# Minimum_System_Destama_RN_21507334088.net
KiCad netlist of a schematic drawn in EAGLE
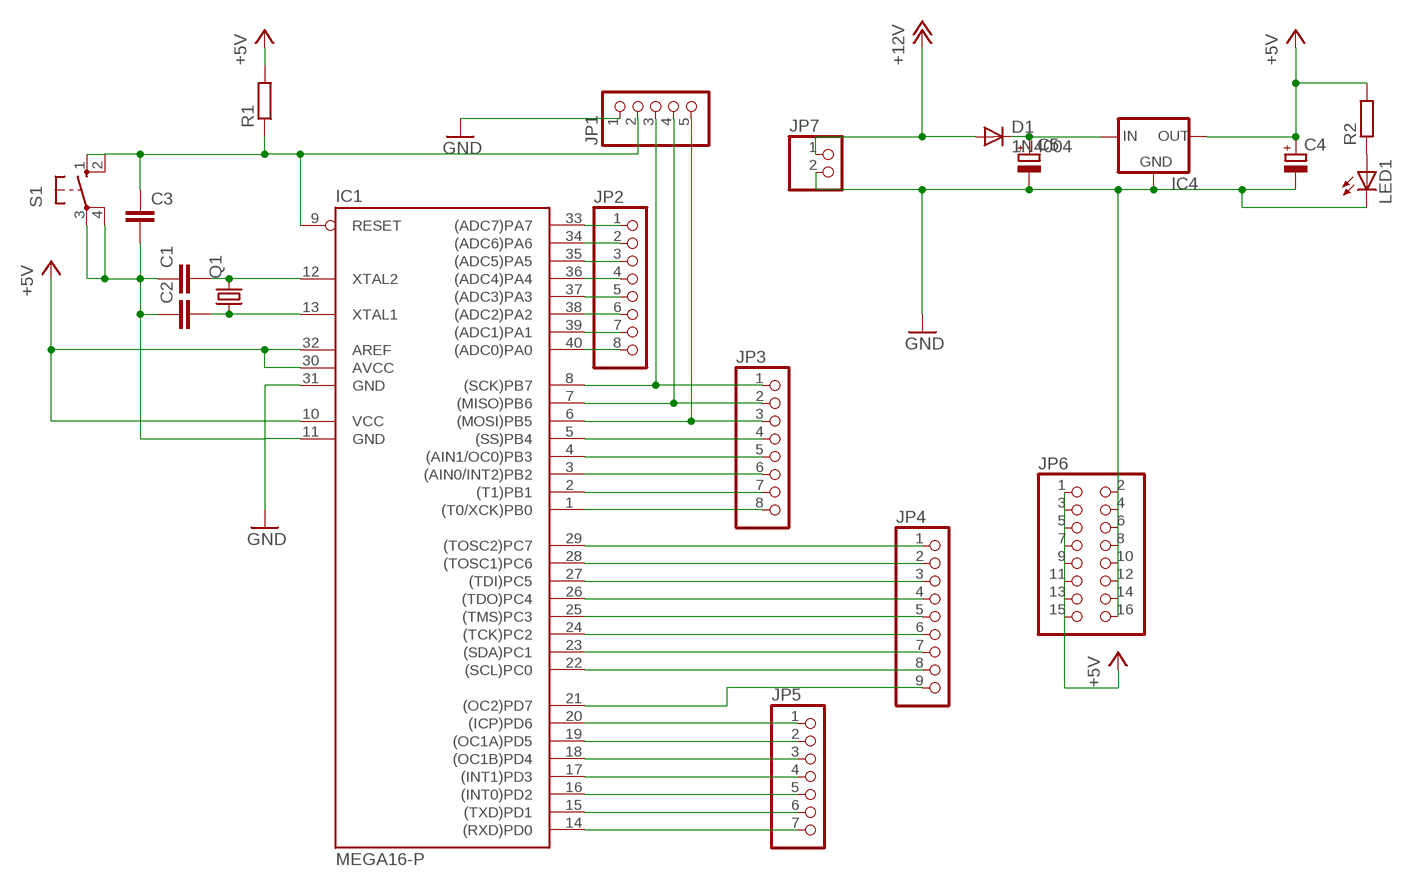
[diagram p0: schematic, sheet 1]

(export (version "E")
  (design (tool "Eeschema 10.0.6"))
  (components
    (comp (ref "C1")
      (value "C-EU025-024X044")
      (footprint "eagle-import:C025-024X044")
      (libsource (lib "eagle-import") (part "C-EU025-024X044"))
    )
    (comp (ref "C2")
      (value "C-EU025-024X044")
      (footprint "eagle-import:C025-024X044")
      (libsource (lib "eagle-import") (part "C-EU025-024X044"))
    )
    (comp (ref "C3")
      (value "C-EU050-025X075")
      (footprint "eagle-import:C050-025X075")
      (libsource (lib "eagle-import") (part "resistor_C-EU050-025X075"))
    )
    (comp (ref "C4")
      (value "CPOL-EUE2.5-5")
      (footprint "eagle-import:E2,5-5")
      (libsource (lib "eagle-import") (part "CPOL-EUE2.5-5"))
    )
    (comp (ref "C5")
      (value "CPOL-EUE2.5-5")
      (footprint "eagle-import:E2,5-5")
      (libsource (lib "eagle-import") (part "CPOL-EUE2.5-5"))
    )
    (comp (ref "D1")
      (value "1N4004")
      (footprint "eagle-import:DO41-10")
      (libsource (lib "eagle-import") (part "1N4004"))
    )
    (comp (ref "IC1")
      (value "MEGA16-P")
      (footprint "eagle-import:DIL40")
      (fields (field (name "MPN") "ATMEGA16-16PU"))
      (libsource (lib "eagle-import") (part "MEGA16-P"))
    )
    (comp (ref "IC4")
      (value "78XXS")
      (footprint "eagle-import:78XXS")
      (libsource (lib "eagle-import") (part "78XXS"))
    )
    (comp (ref "JP1")
      (value "PINHD-1X5")
      (footprint "eagle-import:1X05")
      (libsource (lib "eagle-import") (part "PINHD-1X5"))
    )
    (comp (ref "JP2")
      (value "PINHD-1X8")
      (footprint "eagle-import:1X08")
      (libsource (lib "eagle-import") (part "PINHD-1X8"))
    )
    (comp (ref "JP3")
      (value "PINHD-1X8")
      (footprint "eagle-import:1X08")
      (libsource (lib "eagle-import") (part "PINHD-1X8"))
    )
    (comp (ref "JP4")
      (value "PINHD-1X9")
      (footprint "eagle-import:1X09")
      (libsource (lib "eagle-import") (part "PINHD-1X9"))
    )
    (comp (ref "JP5")
      (value "PINHD-1X7")
      (footprint "eagle-import:1X07")
      (libsource (lib "eagle-import") (part "PINHD-1X7"))
    )
    (comp (ref "JP6")
      (value "PINHD-2X8")
      (footprint "eagle-import:2X08")
      (libsource (lib "eagle-import") (part "PINHD-2X8"))
    )
    (comp (ref "JP7")
      (value "PINHD-1X2")
      (footprint "eagle-import:1X02")
      (libsource (lib "eagle-import") (part "PINHD-1X2"))
    )
    (comp (ref "LED1")
      (value "LED5MM")
      (footprint "eagle-import:LED5MM")
      (libsource (lib "eagle-import") (part "LED5MM"))
    )
    (comp (ref "Q1")
      (value "CRYSTALHC49U-V")
      (footprint "eagle-import:HC49U-V")
      (libsource (lib "eagle-import") (part "CRYSTALHC49U-V"))
    )
    (comp (ref "R1")
      (value "R-EU_0204/7")
      (footprint "eagle-import:0204_7")
      (libsource (lib "eagle-import") (part "R-EU_0204/7"))
    )
    (comp (ref "R2")
      (value "R-EU_0204/7")
      (footprint "eagle-import:0204_7")
      (libsource (lib "eagle-import") (part "R-EU_0204/7"))
    )
    (comp (ref "S1")
      (value "10-XX")
      (footprint "eagle-import:B3F-10XX")
      (fields (field (name "MPN") "B3F-1000"))
      (libsource (lib "eagle-import") (part "10-XX"))
    )
  )
  (nets
    (net (code "1") (name "+5V") (class "Default")
      (node (ref "C4") (pin "+") (pinfunction "+_+") (pintype "passive"))
      (node (ref "IC1") (pin "10") (pinfunction "VCC_10") (pintype "power_in"))
      (node (ref "IC1") (pin "30") (pinfunction "AVCC_30") (pintype "power_in"))
      (node (ref "IC1") (pin "32") (pinfunction "AREF_32") (pintype "passive"))
      (node (ref "IC4") (pin "OUT") (pinfunction "OUT_OUT") (pintype "passive"))
      (node (ref "JP6") (pin "1") (pinfunction "1_1") (pintype "passive"))
      (node (ref "JP6") (pin "11") (pinfunction "11_11") (pintype "passive"))
      (node (ref "JP6") (pin "13") (pinfunction "13_13") (pintype "passive"))
      (node (ref "JP6") (pin "15") (pinfunction "15_15") (pintype "passive"))
      (node (ref "JP6") (pin "3") (pinfunction "3_3") (pintype "passive"))
      (node (ref "JP6") (pin "5") (pinfunction "5_5") (pintype "passive"))
      (node (ref "JP6") (pin "7") (pinfunction "7_7") (pintype "passive"))
      (node (ref "JP6") (pin "9") (pinfunction "9_9") (pintype "passive"))
      (node (ref "R1") (pin "2") (pinfunction "2_2") (pintype "passive"))
      (node (ref "R2") (pin "2") (pinfunction "2_2") (pintype "passive"))
    )
    (net (code "2") (name "+12V") (class "Default")
      (node (ref "D1") (pin "A") (pinfunction "A_A") (pintype "passive"))
      (node (ref "JP7") (pin "1") (pinfunction "1_1") (pintype "passive"))
    )
    (net (code "3") (name "GND") (class "Default")
      (node (ref "C1") (pin "1") (pinfunction "1_1") (pintype "passive"))
      (node (ref "C2") (pin "1") (pinfunction "1_1") (pintype "passive"))
      (node (ref "C3") (pin "2") (pinfunction "2_2") (pintype "passive"))
      (node (ref "C4") (pin "-") (pinfunction "-_-") (pintype "passive"))
      (node (ref "C5") (pin "-") (pinfunction "-_-") (pintype "passive"))
      (node (ref "IC1") (pin "11") (pinfunction "GND_11") (pintype "power_in"))
      (node (ref "IC1") (pin "31") (pinfunction "GND_31") (pintype "power_in"))
      (node (ref "IC4") (pin "GND") (pinfunction "GND_GND") (pintype "input"))
      (node (ref "JP1") (pin "1") (pinfunction "1_1") (pintype "passive"))
      (node (ref "JP6") (pin "10") (pinfunction "10_10") (pintype "passive"))
      (node (ref "JP6") (pin "12") (pinfunction "12_12") (pintype "passive"))
      (node (ref "JP6") (pin "14") (pinfunction "14_14") (pintype "passive"))
      (node (ref "JP6") (pin "16") (pinfunction "16_16") (pintype "passive"))
      (node (ref "JP6") (pin "2") (pinfunction "2_2") (pintype "passive"))
      (node (ref "JP6") (pin "4") (pinfunction "4_4") (pintype "passive"))
      (node (ref "JP6") (pin "6") (pinfunction "6_6") (pintype "passive"))
      (node (ref "JP6") (pin "8") (pinfunction "8_8") (pintype "passive"))
      (node (ref "JP7") (pin "2") (pinfunction "2_2") (pintype "passive"))
      (node (ref "LED1") (pin "K") (pinfunction "C_K") (pintype "passive"))
      (node (ref "S1") (pin "3") (pinfunction "P_3") (pintype "passive"))
      (node (ref "S1") (pin "4") (pinfunction "P1_4") (pintype "passive"))
    )
    (net (code "4") (name "Net-(C5-Pad+)") (class "Default")
      (node (ref "C5") (pin "+") (pinfunction "+_+") (pintype "passive"))
      (node (ref "D1") (pin "C") (pinfunction "C_C") (pintype "passive"))
      (node (ref "IC4") (pin "IN") (pinfunction "IN_IN") (pintype "input"))
    )
    (net (code "5") (name "Net-(IC1-(ADC0)PA0)") (class "Default")
      (node (ref "IC1") (pin "40") (pinfunction "(ADC0)PA0_40") (pintype "bidirectional"))
      (node (ref "JP2") (pin "8") (pinfunction "8_8") (pintype "passive"))
    )
    (net (code "6") (name "Net-(IC1-(ADC1)PA1)") (class "Default")
      (node (ref "IC1") (pin "39") (pinfunction "(ADC1)PA1_39") (pintype "bidirectional"))
      (node (ref "JP2") (pin "7") (pinfunction "7_7") (pintype "passive"))
    )
    (net (code "7") (name "Net-(IC1-(ADC2)PA2)") (class "Default")
      (node (ref "IC1") (pin "38") (pinfunction "(ADC2)PA2_38") (pintype "bidirectional"))
      (node (ref "JP2") (pin "6") (pinfunction "6_6") (pintype "passive"))
    )
    (net (code "8") (name "Net-(IC1-(ADC3)PA3)") (class "Default")
      (node (ref "IC1") (pin "37") (pinfunction "(ADC3)PA3_37") (pintype "bidirectional"))
      (node (ref "JP2") (pin "5") (pinfunction "5_5") (pintype "passive"))
    )
    (net (code "9") (name "Net-(IC1-(ADC4)PA4)") (class "Default")
      (node (ref "IC1") (pin "36") (pinfunction "(ADC4)PA4_36") (pintype "bidirectional"))
      (node (ref "JP2") (pin "4") (pinfunction "4_4") (pintype "passive"))
    )
    (net (code "10") (name "Net-(IC1-(ADC5)PA5)") (class "Default")
      (node (ref "IC1") (pin "35") (pinfunction "(ADC5)PA5_35") (pintype "bidirectional"))
      (node (ref "JP2") (pin "3") (pinfunction "3_3") (pintype "passive"))
    )
    (net (code "11") (name "Net-(IC1-(ADC6)PA6)") (class "Default")
      (node (ref "IC1") (pin "34") (pinfunction "(ADC6)PA6_34") (pintype "bidirectional"))
      (node (ref "JP2") (pin "2") (pinfunction "2_2") (pintype "passive"))
    )
    (net (code "12") (name "Net-(IC1-(ADC7)PA7)") (class "Default")
      (node (ref "IC1") (pin "33") (pinfunction "(ADC7)PA7_33") (pintype "bidirectional"))
      (node (ref "JP2") (pin "1") (pinfunction "1_1") (pintype "passive"))
    )
    (net (code "13") (name "Net-(IC1-(AIN0{slash}INT2)PB2)") (class "Default")
      (node (ref "IC1") (pin "3") (pinfunction "(AIN0/INT2)PB2_3") (pintype "bidirectional"))
      (node (ref "JP3") (pin "6") (pinfunction "6_6") (pintype "passive"))
    )
    (net (code "14") (name "Net-(IC1-(AIN1{slash}OC0)PB3)") (class "Default")
      (node (ref "IC1") (pin "4") (pinfunction "(AIN1/OC0)PB3_4") (pintype "bidirectional"))
      (node (ref "JP3") (pin "5") (pinfunction "5_5") (pintype "passive"))
    )
    (net (code "15") (name "Net-(IC1-(ICP)PD6)") (class "Default")
      (node (ref "IC1") (pin "20") (pinfunction "(ICP)PD6_20") (pintype "bidirectional"))
      (node (ref "JP5") (pin "1") (pinfunction "1_1") (pintype "passive"))
    )
    (net (code "16") (name "Net-(IC1-(INT0)PD2)") (class "Default")
      (node (ref "IC1") (pin "16") (pinfunction "(INT0)PD2_16") (pintype "bidirectional"))
      (node (ref "JP5") (pin "5") (pinfunction "5_5") (pintype "passive"))
    )
    (net (code "17") (name "Net-(IC1-(INT1)PD3)") (class "Default")
      (node (ref "IC1") (pin "17") (pinfunction "(INT1)PD3_17") (pintype "bidirectional"))
      (node (ref "JP5") (pin "4") (pinfunction "4_4") (pintype "passive"))
    )
    (net (code "18") (name "Net-(IC1-(MISO)PB6)") (class "Default")
      (node (ref "IC1") (pin "7") (pinfunction "(MISO)PB6_7") (pintype "bidirectional"))
      (node (ref "JP1") (pin "4") (pinfunction "4_4") (pintype "passive"))
      (node (ref "JP3") (pin "2") (pinfunction "2_2") (pintype "passive"))
    )
    (net (code "19") (name "Net-(IC1-(MOSI)PB5)") (class "Default")
      (node (ref "IC1") (pin "6") (pinfunction "(MOSI)PB5_6") (pintype "bidirectional"))
      (node (ref "JP1") (pin "5") (pinfunction "5_5") (pintype "passive"))
      (node (ref "JP3") (pin "3") (pinfunction "3_3") (pintype "passive"))
    )
    (net (code "20") (name "Net-(IC1-(OC1A)PD5)") (class "Default")
      (node (ref "IC1") (pin "19") (pinfunction "(OC1A)PD5_19") (pintype "bidirectional"))
      (node (ref "JP5") (pin "2") (pinfunction "2_2") (pintype "passive"))
    )
    (net (code "21") (name "Net-(IC1-(OC1B)PD4)") (class "Default")
      (node (ref "IC1") (pin "18") (pinfunction "(OC1B)PD4_18") (pintype "bidirectional"))
      (node (ref "JP5") (pin "3") (pinfunction "3_3") (pintype "passive"))
    )
    (net (code "22") (name "Net-(IC1-(OC2)PD7)") (class "Default")
      (node (ref "IC1") (pin "21") (pinfunction "(OC2)PD7_21") (pintype "bidirectional"))
      (node (ref "JP4") (pin "9") (pinfunction "9_9") (pintype "passive"))
    )
    (net (code "23") (name "Net-(IC1-(RXD)PD0)") (class "Default")
      (node (ref "IC1") (pin "14") (pinfunction "(RXD)PD0_14") (pintype "bidirectional"))
      (node (ref "JP5") (pin "7") (pinfunction "7_7") (pintype "passive"))
    )
    (net (code "24") (name "Net-(IC1-(SCK)PB7)") (class "Default")
      (node (ref "IC1") (pin "8") (pinfunction "(SCK)PB7_8") (pintype "bidirectional"))
      (node (ref "JP1") (pin "3") (pinfunction "3_3") (pintype "passive"))
      (node (ref "JP3") (pin "1") (pinfunction "1_1") (pintype "passive"))
    )
    (net (code "25") (name "Net-(IC1-(SCL)PC0)") (class "Default")
      (node (ref "IC1") (pin "22") (pinfunction "(SCL)PC0_22") (pintype "bidirectional"))
      (node (ref "JP4") (pin "8") (pinfunction "8_8") (pintype "passive"))
    )
    (net (code "26") (name "Net-(IC1-(SDA)PC1)") (class "Default")
      (node (ref "IC1") (pin "23") (pinfunction "(SDA)PC1_23") (pintype "bidirectional"))
      (node (ref "JP4") (pin "7") (pinfunction "7_7") (pintype "passive"))
    )
    (net (code "27") (name "Net-(IC1-(SS)PB4)") (class "Default")
      (node (ref "IC1") (pin "5") (pinfunction "(SS)PB4_5") (pintype "bidirectional"))
      (node (ref "JP3") (pin "4") (pinfunction "4_4") (pintype "passive"))
    )
    (net (code "28") (name "Net-(IC1-(T0{slash}XCK)PB0)") (class "Default")
      (node (ref "IC1") (pin "1") (pinfunction "(T0/XCK)PB0_1") (pintype "bidirectional"))
      (node (ref "JP3") (pin "8") (pinfunction "8_8") (pintype "passive"))
    )
    (net (code "29") (name "Net-(IC1-(T1)PB1)") (class "Default")
      (node (ref "IC1") (pin "2") (pinfunction "(T1)PB1_2") (pintype "bidirectional"))
      (node (ref "JP3") (pin "7") (pinfunction "7_7") (pintype "passive"))
    )
    (net (code "30") (name "Net-(IC1-(TCK)PC2)") (class "Default")
      (node (ref "IC1") (pin "24") (pinfunction "(TCK)PC2_24") (pintype "bidirectional"))
      (node (ref "JP4") (pin "6") (pinfunction "6_6") (pintype "passive"))
    )
    (net (code "31") (name "Net-(IC1-(TDI)PC5)") (class "Default")
      (node (ref "IC1") (pin "27") (pinfunction "(TDI)PC5_27") (pintype "bidirectional"))
      (node (ref "JP4") (pin "3") (pinfunction "3_3") (pintype "passive"))
    )
    (net (code "32") (name "Net-(IC1-(TDO)PC4)") (class "Default")
      (node (ref "IC1") (pin "26") (pinfunction "(TDO)PC4_26") (pintype "bidirectional"))
      (node (ref "JP4") (pin "4") (pinfunction "4_4") (pintype "passive"))
    )
    (net (code "33") (name "Net-(IC1-(TMS)PC3)") (class "Default")
      (node (ref "IC1") (pin "25") (pinfunction "(TMS)PC3_25") (pintype "bidirectional"))
      (node (ref "JP4") (pin "5") (pinfunction "5_5") (pintype "passive"))
    )
    (net (code "34") (name "Net-(IC1-(TOSC1)PC6)") (class "Default")
      (node (ref "IC1") (pin "28") (pinfunction "(TOSC1)PC6_28") (pintype "bidirectional"))
      (node (ref "JP4") (pin "2") (pinfunction "2_2") (pintype "passive"))
    )
    (net (code "35") (name "Net-(IC1-(TOSC2)PC7)") (class "Default")
      (node (ref "IC1") (pin "29") (pinfunction "(TOSC2)PC7_29") (pintype "bidirectional"))
      (node (ref "JP4") (pin "1") (pinfunction "1_1") (pintype "passive"))
    )
    (net (code "36") (name "Net-(IC1-(TXD)PD1)") (class "Default")
      (node (ref "IC1") (pin "15") (pinfunction "(TXD)PD1_15") (pintype "bidirectional"))
      (node (ref "JP5") (pin "6") (pinfunction "6_6") (pintype "passive"))
    )
    (net (code "37") (name "Net-(IC1-RESET)") (class "Default")
      (node (ref "C3") (pin "1") (pinfunction "1_1") (pintype "passive"))
      (node (ref "IC1") (pin "9") (pinfunction "RESET_9") (pintype "input"))
      (node (ref "JP1") (pin "2") (pinfunction "2_2") (pintype "passive"))
      (node (ref "R1") (pin "1") (pinfunction "1_1") (pintype "passive"))
      (node (ref "S1") (pin "1") (pinfunction "S_1") (pintype "passive"))
      (node (ref "S1") (pin "2") (pinfunction "S1_2") (pintype "passive"))
    )
    (net (code "38") (name "Net-(IC1-XTAL1)") (class "Default")
      (node (ref "C2") (pin "2") (pinfunction "2_2") (pintype "passive"))
      (node (ref "IC1") (pin "13") (pinfunction "XTAL1_13") (pintype "bidirectional"))
      (node (ref "Q1") (pin "1") (pinfunction "1_1") (pintype "passive"))
    )
    (net (code "39") (name "Net-(IC1-XTAL2)") (class "Default")
      (node (ref "C1") (pin "2") (pinfunction "2_2") (pintype "passive"))
      (node (ref "IC1") (pin "12") (pinfunction "XTAL2_12") (pintype "bidirectional"))
      (node (ref "Q1") (pin "2") (pinfunction "2_2") (pintype "passive"))
    )
    (net (code "40") (name "Net-(LED1-PadA)") (class "Default")
      (node (ref "LED1") (pin "A") (pinfunction "A_A") (pintype "passive"))
      (node (ref "R2") (pin "1") (pinfunction "1_1") (pintype "passive"))
    )
  )
)
